# Cerebro_4_8.net
KiCad netlist of a schematic drawn in EAGLE
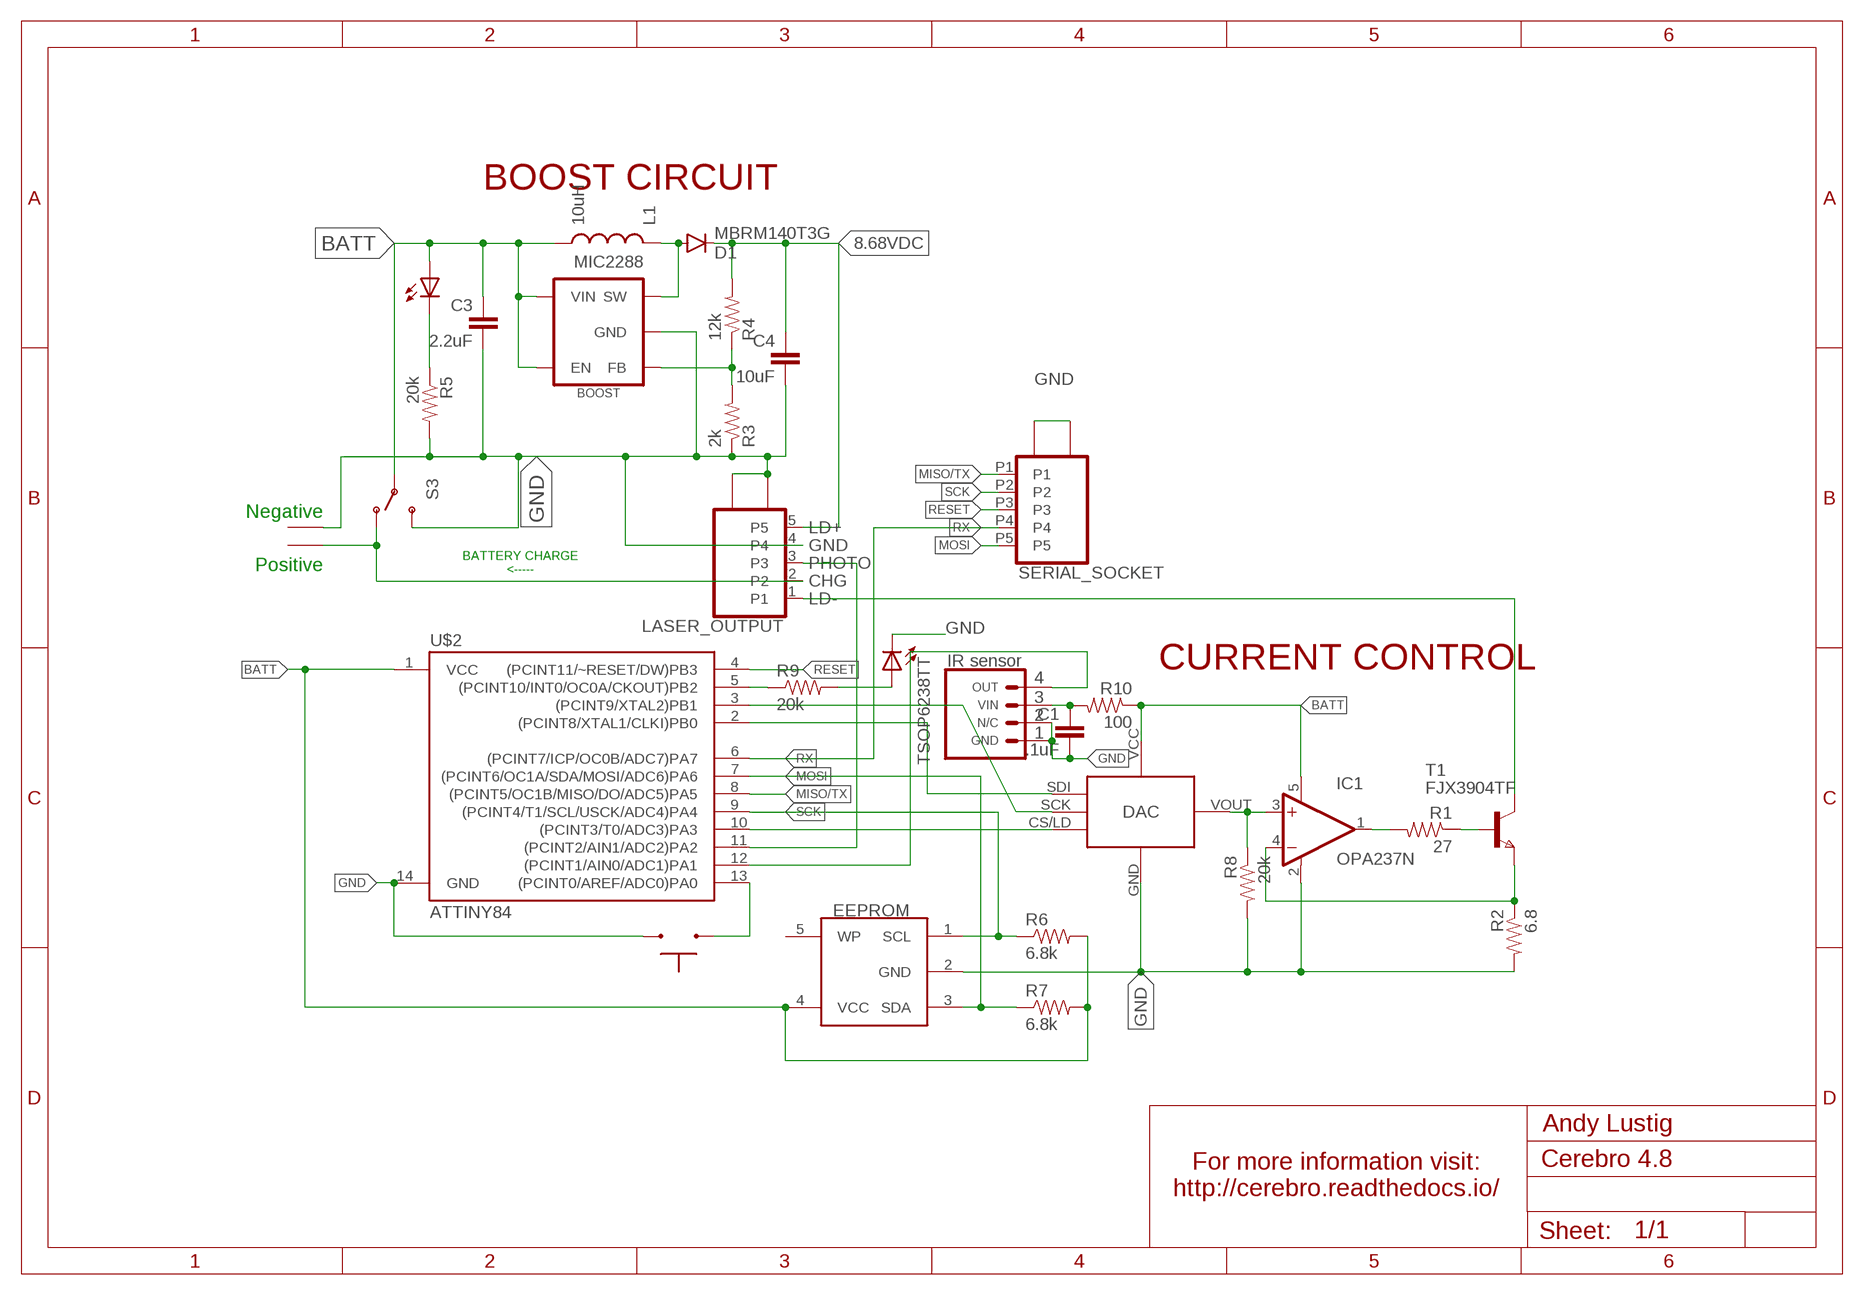
[diagram p0: schematic, sheet 1]

(export (version "E")
  (design (tool "Eeschema 10.0.6"))
  (components
    (comp (ref "C1")
      (value ".1uF")
      (footprint "eagle-import:0603-CAP")
      (libsource (lib "eagle-import") (part "CAP0603-CAP"))
    )
    (comp (ref "C3")
      (value "2.2uF")
      (footprint "eagle-import:0805")
      (libsource (lib "eagle-import") (part "CAP0805"))
    )
    (comp (ref "C4")
      (value "10uF")
      (footprint "eagle-import:0805")
      (libsource (lib "eagle-import") (part "CAP0805"))
    )
    (comp (ref "D1")
      (value "MBRM140T3G")
      (footprint "eagle-import:POWERMITE")
      (libsource (lib "eagle-import") (part "DIODEPOWERMITE"))
    )
    (comp (ref "GROUND")
      (value "BATT_TERMINAL")
      (footprint "eagle-import:BATT_TERMINAL")
      (libsource (lib "eagle-import") (part "BATT_TERMINAL"))
    )
    (comp (ref "IC1")
      (value "OPA237N")
      (footprint "eagle-import:SOT23-5")
      (fields (field (name "MF") "TEXAS INSTRUMENTS") (field (name "MPN") "OPA237NA/250"))
      (libsource (lib "eagle-import") (part "OPA237N"))
    )
    (comp (ref "INDICATOR_LED")
      (value "LED")
      (footprint "eagle-import:CHIP-LED0603")
      (libsource (lib "eagle-import") (part "LEDCHIP-LED0603"))
    )
    (comp (ref "INDICATOR_LED1")
      (value "LED")
      (footprint "eagle-import:CHIP-LED0603")
      (libsource (lib "eagle-import") (part "LEDCHIP-LED0603"))
    )
    (comp (ref "L1")
      (value "10uH")
      (footprint "eagle-import:1812")
      (libsource (lib "eagle-import") (part "INDUCTORLQH4"))
    )
    (comp (ref "LASER_OUTPUT")
      (value "USB_MICROB_PLUG-PTH2")
      (footprint "eagle-import:MICRO-B-TH")
      (libsource (lib "eagle-import") (part "USB_MICROB_PLUG-PTH2"))
    )
    (comp (ref "MIC2288")
      (value "BOOST")
      (footprint "eagle-import:SOT23-5")
      (libsource (lib "eagle-import") (part "BOOST_CONVERTER"))
    )
    (comp (ref "R1")
      (value "27")
      (footprint "eagle-import:0603-RES")
      (libsource (lib "eagle-import") (part "RESISTOR0603-RES"))
    )
    (comp (ref "R2")
      (value "6.8")
      (footprint "eagle-import:0603-RES")
      (libsource (lib "eagle-import") (part "RESISTOR0603-RES"))
    )
    (comp (ref "R3")
      (value "2k")
      (footprint "eagle-import:0603-RES")
      (libsource (lib "eagle-import") (part "RESISTOR0603-RES"))
    )
    (comp (ref "R4")
      (value "12k")
      (footprint "eagle-import:0603-RES")
      (libsource (lib "eagle-import") (part "RESISTOR0603-RES"))
    )
    (comp (ref "R5")
      (value "20k")
      (footprint "eagle-import:0603-RES")
      (libsource (lib "eagle-import") (part "RESISTOR0603-RES"))
    )
    (comp (ref "R6")
      (value "6.8k")
      (footprint "eagle-import:0603-RES")
      (libsource (lib "eagle-import") (part "RESISTOR0603-RES"))
    )
    (comp (ref "R7")
      (value "6.8k")
      (footprint "eagle-import:0603-RES")
      (libsource (lib "eagle-import") (part "RESISTOR0603-RES"))
    )
    (comp (ref "R8")
      (value "20k")
      (footprint "eagle-import:0603-RES")
      (libsource (lib "eagle-import") (part "RESISTOR0603-RES"))
    )
    (comp (ref "R9")
      (value "20k")
      (footprint "eagle-import:0603-RES")
      (libsource (lib "eagle-import") (part "RESISTOR0603-RES"))
    )
    (comp (ref "R10")
      (value "100")
      (footprint "eagle-import:0603-RES")
      (libsource (lib "eagle-import") (part "RESISTOR0603-RES"))
    )
    (comp (ref "S3")
      (value "SWITCH-SPDTSMD2")
      (footprint "eagle-import:SWITCH-SPDT-SMD")
      (libsource (lib "eagle-import") (part "SWITCH-SPDTSMD2"))
    )
    (comp (ref "SDF")
      (value "TSOP6238TT")
      (footprint "eagle-import:TSOP6")
      (libsource (lib "eagle-import") (part "TSOP6238TT"))
    )
    (comp (ref "SERIAL_SOCKET")
      (value "USB_SOCKET_MICRO_VERTREINFORCED")
      (footprint "eagle-import:USB_HORZ_REINFORCED_MICRO")
      (libsource (lib "eagle-import") (part "USB_SOCKET_MICRO_VERTREINFORCED"))
    )
    (comp (ref "T1")
      (value "FJX3904TF")
      (footprint "eagle-import:SOT323")
      (fields (field (name "MPN") "DSS4160U-7"))
      (libsource (lib "eagle-import") (part "NPNSOT323"))
    )
    (comp (ref "U$1")
      (value "DAC_LTC2630")
      (footprint "eagle-import:SC-70")
      (libsource (lib "eagle-import") (part "DAC_LTC2630"))
    )
    (comp (ref "U$2")
      (value "ATTINY84")
      (footprint "eagle-import:SO14")
      (libsource (lib "eagle-import") (part "ATTINY84"))
    )
    (comp (ref "U$3")
      (value "SWITCH-MOMENTARY-NO")
      (footprint "eagle-import:SWITCH_MOMENTARY_XS")
      (libsource (lib "eagle-import") (part "SWITCH-MOMENTARY-NO"))
    )
    (comp (ref "U$4")
      (value "EEPROM24C64A")
      (footprint "eagle-import:SOT23-5")
      (libsource (lib "eagle-import") (part "EEPROM24C64A"))
    )
    (comp (ref "U$8")
      (value "BATT_TERMINAL")
      (footprint "eagle-import:BATT_TERMINAL")
      (libsource (lib "eagle-import") (part "BATT_TERMINAL"))
    )
  )
  (nets
    (net (code "1") (name "8.68VDC") (class "Default")
      (node (ref "C4") (pin "1") (pinfunction "1_1") (pintype "passive"))
      (node (ref "D1") (pin "CATHODE") (pinfunction "C_CATHODE") (pintype "passive"))
      (node (ref "LASER_OUTPUT") (pin "5") (pinfunction "P5_5") (pintype "bidirectional"))
      (node (ref "R4") (pin "2") (pinfunction "2_2") (pintype "passive"))
    )
    (net (code "2") (name "BATT") (class "Default")
      (node (ref "C3") (pin "1") (pinfunction "1_1") (pintype "passive"))
      (node (ref "IC1") (pin "5") (pinfunction "V+_5") (pintype "power_in"))
      (node (ref "INDICATOR_LED") (pin "A") (pinfunction "A_A") (pintype "passive"))
      (node (ref "L1") (pin "P$2") (pinfunction "2_P$2") (pintype "passive"))
      (node (ref "L1") (pin "P$4") (pinfunction "2_P$4") (pintype "passive"))
      (node (ref "MIC2288") (pin "4") (pinfunction "EN_4") (pintype "input"))
      (node (ref "MIC2288") (pin "5") (pinfunction "VIN_5") (pintype "passive"))
      (node (ref "R10") (pin "1") (pinfunction "1_1") (pintype "passive"))
      (node (ref "R6") (pin "2") (pinfunction "2_2") (pintype "passive"))
      (node (ref "R7") (pin "2") (pinfunction "2_2") (pintype "passive"))
      (node (ref "S3") (pin "2") (pinfunction "P_2") (pintype "passive"))
      (node (ref "U$1") (pin "VCC") (pinfunction "VIN_VCC") (pintype "bidirectional"))
      (node (ref "U$2") (pin "1") (pinfunction "VCC_1") (pintype "bidirectional"))
      (node (ref "U$4") (pin "4") (pinfunction "VCC_4") (pintype "bidirectional"))
    )
    (net (code "3") (name "GND") (class "Default")
      (node (ref "C1") (pin "2") (pinfunction "2_2") (pintype "passive"))
      (node (ref "C3") (pin "2") (pinfunction "2_2") (pintype "passive"))
      (node (ref "C4") (pin "2") (pinfunction "2_2") (pintype "passive"))
      (node (ref "GROUND") (pin "P$1") (pinfunction "P$1_P$1") (pintype "power_in"))
      (node (ref "IC1") (pin "2") (pinfunction "V-_2") (pintype "power_in"))
      (node (ref "INDICATOR_LED1") (pin "C") (pinfunction "C_C") (pintype "passive"))
      (node (ref "LASER_OUTPUT") (pin "4") (pinfunction "P4_4") (pintype "bidirectional"))
      (node (ref "LASER_OUTPUT") (pin "P$1") (pinfunction "P$1_P$1") (pintype "bidirectional"))
      (node (ref "LASER_OUTPUT") (pin "P$2") (pinfunction "P$2_P$2") (pintype "bidirectional"))
      (node (ref "MIC2288") (pin "2") (pinfunction "GND_2") (pintype "input"))
      (node (ref "R2") (pin "2") (pinfunction "2_2") (pintype "passive"))
      (node (ref "R3") (pin "1") (pinfunction "1_1") (pintype "passive"))
      (node (ref "R5") (pin "2") (pinfunction "2_2") (pintype "passive"))
      (node (ref "R8") (pin "2") (pinfunction "2_2") (pintype "passive"))
      (node (ref "S3") (pin "3") (pinfunction "S_3") (pintype "passive"))
      (node (ref "SDF") (pin "P$1") (pinfunction "1_P$1") (pintype "passive"))
      (node (ref "SDF") (pin "P$2") (pinfunction "2_P$2") (pintype "passive"))
      (node (ref "SERIAL_SOCKET") (pin "G1") (pinfunction "P$1_G1") (pintype "bidirectional"))
      (node (ref "SERIAL_SOCKET") (pin "G2") (pinfunction "P$1_G2") (pintype "bidirectional"))
      (node (ref "SERIAL_SOCKET") (pin "P$1") (pinfunction "P$2_P$1") (pintype "bidirectional"))
      (node (ref "SERIAL_SOCKET") (pin "P$2") (pinfunction "P$2_P$2") (pintype "bidirectional"))
      (node (ref "U$1") (pin "GND") (pinfunction "GND_GND") (pintype "bidirectional"))
      (node (ref "U$2") (pin "14") (pinfunction "GND_14") (pintype "bidirectional"))
      (node (ref "U$3") (pin "P$2") (pinfunction "2_P$2") (pintype "bidirectional"))
      (node (ref "U$4") (pin "2") (pinfunction "GND_2") (pintype "bidirectional"))
    )
    (net (code "4") (name "MISO{slash}TX") (class "Default")
      (node (ref "SERIAL_SOCKET") (pin "P1") (pinfunction "P1_P1") (pintype "bidirectional"))
      (node (ref "U$2") (pin "8") (pinfunction "(PCINT5/OC1B/MISO/DO/ADC5)PA5_8") (pintype "bidirectional"))
    )
    (net (code "5") (name "MOSI") (class "Default")
      (node (ref "R7") (pin "1") (pinfunction "1_1") (pintype "passive"))
      (node (ref "SERIAL_SOCKET") (pin "P5") (pinfunction "P5_P5") (pintype "bidirectional"))
      (node (ref "U$2") (pin "7") (pinfunction "(PCINT6/OC1A/SDA/MOSI/ADC6)PA6_7") (pintype "bidirectional"))
      (node (ref "U$4") (pin "3") (pinfunction "SDA_3") (pintype "bidirectional"))
    )
    (net (code "6") (name "Net-(D1-A)") (class "Default")
      (node (ref "D1") (pin "ANODE") (pinfunction "A_ANODE") (pintype "passive"))
      (node (ref "L1") (pin "P$1") (pinfunction "1_P$1") (pintype "passive"))
      (node (ref "L1") (pin "P$3") (pinfunction "1_P$3") (pintype "passive"))
      (node (ref "MIC2288") (pin "1") (pinfunction "SW_1") (pintype "input"))
    )
    (net (code "7") (name "Net-(IC1-+IN)") (class "Default")
      (node (ref "IC1") (pin "3") (pinfunction "+IN_3") (pintype "input"))
      (node (ref "R8") (pin "1") (pinfunction "1_1") (pintype "passive"))
      (node (ref "U$1") (pin "VOUT") (pinfunction "VOUT_VOUT") (pintype "bidirectional"))
    )
    (net (code "8") (name "Net-(IC1--IN)") (class "Default")
      (node (ref "IC1") (pin "4") (pinfunction "-IN_4") (pintype "input"))
      (node (ref "R2") (pin "1") (pinfunction "1_1") (pintype "passive"))
      (node (ref "T1") (pin "3") (pinfunction "E_3") (pintype "passive"))
    )
    (net (code "9") (name "Net-(IC1-OUT)") (class "Default")
      (node (ref "IC1") (pin "1") (pinfunction "OUT_1") (pintype "output"))
      (node (ref "R1") (pin "2") (pinfunction "2_2") (pintype "passive"))
    )
    (net (code "10") (name "Net-(INDICATOR_LED-PadC)") (class "Default")
      (node (ref "INDICATOR_LED") (pin "C") (pinfunction "C_C") (pintype "passive"))
      (node (ref "R5") (pin "1") (pinfunction "1_1") (pintype "passive"))
    )
    (net (code "11") (name "Net-(INDICATOR_LED1-PadA)") (class "Default")
      (node (ref "INDICATOR_LED1") (pin "A") (pinfunction "A_A") (pintype "passive"))
      (node (ref "R9") (pin "2") (pinfunction "2_2") (pintype "passive"))
    )
    (net (code "12") (name "Net-(LASER_OUTPUT-P1)") (class "Default")
      (node (ref "LASER_OUTPUT") (pin "1") (pinfunction "P1_1") (pintype "bidirectional"))
      (node (ref "T1") (pin "1") (pinfunction "C_1") (pintype "passive"))
    )
    (net (code "13") (name "Net-(LASER_OUTPUT-P2)") (class "Default")
      (node (ref "LASER_OUTPUT") (pin "2") (pinfunction "P2_2") (pintype "bidirectional"))
      (node (ref "S3") (pin "1") (pinfunction "O_1") (pintype "passive"))
      (node (ref "U$8") (pin "P$1") (pinfunction "P$1_P$1") (pintype "power_in"))
    )
    (net (code "14") (name "Net-(LASER_OUTPUT-P3)") (class "Default")
      (node (ref "LASER_OUTPUT") (pin "3") (pinfunction "P3_3") (pintype "bidirectional"))
      (node (ref "U$2") (pin "11") (pinfunction "(PCINT2/AIN1/ADC2)PA2_11") (pintype "bidirectional"))
    )
    (net (code "15") (name "Net-(MIC2288-FB)") (class "Default")
      (node (ref "MIC2288") (pin "3") (pinfunction "FB_3") (pintype "input"))
      (node (ref "R3") (pin "2") (pinfunction "2_2") (pintype "passive"))
      (node (ref "R4") (pin "1") (pinfunction "1_1") (pintype "passive"))
    )
    (net (code "16") (name "Net-(SDF-3)") (class "Default")
      (node (ref "C1") (pin "1") (pinfunction "1_1") (pintype "passive"))
      (node (ref "R10") (pin "2") (pinfunction "2_2") (pintype "passive"))
      (node (ref "SDF") (pin "P$3") (pinfunction "3_P$3") (pintype "passive"))
    )
    (net (code "17") (name "Net-(SDF-4)") (class "Default")
      (node (ref "SDF") (pin "P$4") (pinfunction "4_P$4") (pintype "passive"))
      (node (ref "U$2") (pin "12") (pinfunction "(PCINT1/AIN0/ADC1)PA1_12") (pintype "bidirectional"))
    )
    (net (code "18") (name "Net-(T1-B)") (class "Default")
      (node (ref "R1") (pin "1") (pinfunction "1_1") (pintype "passive"))
      (node (ref "T1") (pin "2") (pinfunction "B_2") (pintype "passive"))
    )
    (net (code "19") (name "Net-(U$2-(PCINT0{slash}AREF{slash}ADC0)PA0)") (class "Default")
      (node (ref "U$2") (pin "13") (pinfunction "(PCINT0/AREF/ADC0)PA0_13") (pintype "bidirectional"))
      (node (ref "U$3") (pin "P$1") (pinfunction "1_P$1") (pintype "bidirectional"))
    )
    (net (code "20") (name "Net-(U$2-(PCINT3{slash}T0{slash}ADC3)PA3)") (class "Default")
      (node (ref "U$1") (pin "CS/LD") (pinfunction "CS/LD_CS/LD") (pintype "bidirectional"))
      (node (ref "U$2") (pin "10") (pinfunction "(PCINT3/T0/ADC3)PA3_10") (pintype "bidirectional"))
    )
    (net (code "21") (name "Net-(U$2-(PCINT8{slash}XTAL1{slash}CLKI)PB0)") (class "Default")
      (node (ref "U$1") (pin "SDI") (pinfunction "SDI_SDI") (pintype "bidirectional"))
      (node (ref "U$2") (pin "2") (pinfunction "(PCINT8/XTAL1/CLKI)PB0_2") (pintype "bidirectional"))
    )
    (net (code "22") (name "Net-(U$2-(PCINT9{slash}XTAL2)PB1)") (class "Default")
      (node (ref "U$1") (pin "SCK") (pinfunction "SCK_SCK") (pintype "bidirectional"))
      (node (ref "U$2") (pin "3") (pinfunction "(PCINT9/XTAL2)PB1_3") (pintype "bidirectional"))
    )
    (net (code "23") (name "Net-(U$2-(PCINT10{slash}INT0{slash}OC0A{slash}CKOUT)PB2)") (class "Default")
      (node (ref "R9") (pin "1") (pinfunction "1_1") (pintype "passive"))
      (node (ref "U$2") (pin "5") (pinfunction "(PCINT10/INT0/OC0A/CKOUT)PB2_5") (pintype "bidirectional"))
    )
    (net (code "24") (name "RESET") (class "Default")
      (node (ref "SERIAL_SOCKET") (pin "P3") (pinfunction "P3_P3") (pintype "bidirectional"))
      (node (ref "U$2") (pin "4") (pinfunction "(PCINT11/~{RESET/DW})PB3_4") (pintype "bidirectional"))
    )
    (net (code "25") (name "RX") (class "Default")
      (node (ref "SERIAL_SOCKET") (pin "P4") (pinfunction "P4_P4") (pintype "bidirectional"))
      (node (ref "U$2") (pin "6") (pinfunction "(PCINT7/ICP/OC0B/ADC7)PA7_6") (pintype "bidirectional"))
    )
    (net (code "26") (name "SCK") (class "Default")
      (node (ref "R6") (pin "1") (pinfunction "1_1") (pintype "passive"))
      (node (ref "SERIAL_SOCKET") (pin "P2") (pinfunction "P2_P2") (pintype "bidirectional"))
      (node (ref "U$2") (pin "9") (pinfunction "(PCINT4/T1/SCL/USCK/ADC4)PA4_9") (pintype "bidirectional"))
      (node (ref "U$4") (pin "1") (pinfunction "SCL_1") (pintype "bidirectional"))
    )
    (net (code "27") (name "unconnected-(U$4-WP-Pad5)") (class "Default")
      (node (ref "U$4") (pin "5") (pinfunction "WP_5") (pintype "bidirectional"))
    )
  )
)
